# 3_STM32F103_Debugger.net
KiCad netlist of a schematic drawn in Altium Designer
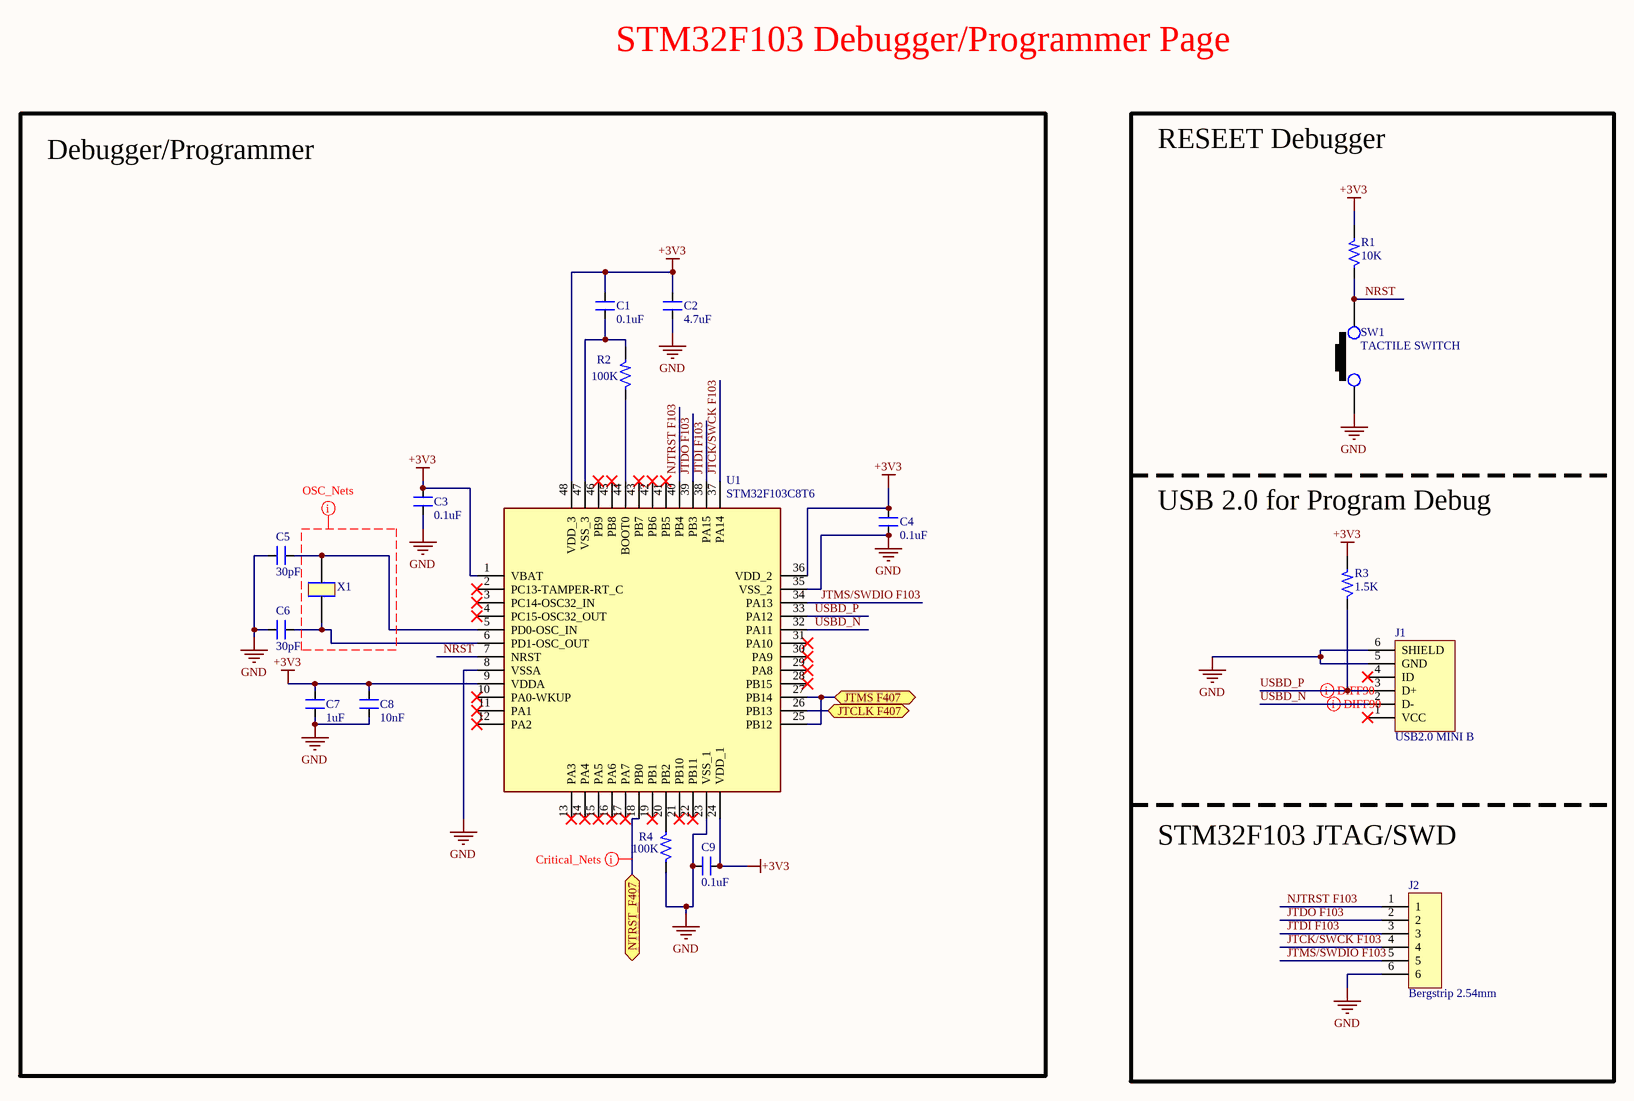
[diagram p0: [3] STM32F103 Debugger.SchDoc]

(export (version "E")
  (design (tool "Eeschema 10.0.6"))
  (components
    (comp (ref "C1")
      (value "0.1uF")
      (footprint "CAP_0805")
      (description "0.1µF ±10% 50V Ceramic Capacitor X7R 0805 (2012 Metric)")
      (fields
        (field (name "MANUFACTURER") "Samsung")
        (field (name "MANUFACTURER PART NUMBER") "CL21B104KBCNNNC")
      )
      (libsource (lib "ESTEEMPCBLIB") (part "CAP_0.1uF-50V-10%-0805"))
    )
    (comp (ref "C2")
      (value "4.7uF")
      (footprint "CAP_0805")
      (description "4.7µF ±10% 50V Ceramic Capacitor X5R 0805 (2012 Metric)")
      (fields
        (field (name "MANUFACTURER") "Yageo")
        (field (name "MANUFACTURER PART NUMBER") "GRM21BR61H475KE51L")
      )
      (libsource (lib "ESTEEMPCBLIB") (part "CAP_4.7uF-50V-10%-0805"))
    )
    (comp (ref "C3")
      (value "0.1uF")
      (footprint "CAP_0805")
      (description "0.1µF ±10% 50V Ceramic Capacitor X7R 0805 (2012 Metric)")
      (fields
        (field (name "MANUFACTURER") "Samsung")
        (field (name "MANUFACTURER PART NUMBER") "CL21B104KBCNNNC")
      )
      (libsource (lib "ESTEEMPCBLIB") (part "CAP_0.1uF-50V-10%-0805"))
    )
    (comp (ref "C4")
      (value "0.1uF")
      (footprint "CAP_0805")
      (description "0.1µF ±10% 50V Ceramic Capacitor X7R 0805 (2012 Metric)")
      (fields
        (field (name "MANUFACTURER") "Samsung")
        (field (name "MANUFACTURER PART NUMBER") "CL21B104KBCNNNC")
      )
      (libsource (lib "ESTEEMPCBLIB") (part "CAP_0.1uF-50V-10%-0805"))
    )
    (comp (ref "C5")
      (value "30pF")
      (footprint "CAP_0805")
      (description "±10% 50V Ceramic Capacitor C0G, NP0 0805 (2012 Metric)")
      (fields
        (field (name "MANUFACTURER PART NUMBER") "C0805C300K5GAC7800")
        (field (name "MANUFACTURER") "KEMET")
      )
      (libsource (lib "ESTEEMPCBLIB") (part "CAP_30pF-50V-10%-0805"))
    )
    (comp (ref "C6")
      (value "30pF")
      (footprint "CAP_0805")
      (description "±10% 50V Ceramic Capacitor C0G, NP0 0805 (2012 Metric)")
      (fields
        (field (name "MANUFACTURER PART NUMBER") "C0805C300K5GAC7800")
        (field (name "MANUFACTURER") "KEMET")
      )
      (libsource (lib "ESTEEMPCBLIB") (part "CAP_30pF-50V-10%-0805"))
    )
    (comp (ref "C7")
      (value "1uF")
      (footprint "CAP_0805")
      (description "1µF ±5% 50V Ceramic Capacitor X7R 0805 (2012 Metric)")
      (fields
        (field (name "MANUFACTURER") "Samsung")
        (field (name "MANUFACTURER PART NUMBER") "CC0805JKX7R9BB105")
      )
      (libsource (lib "ESTEEMPCBLIB") (part "CAP_1uF-50V-5%-0805"))
    )
    (comp (ref "C8")
      (value "10nF")
      (footprint "CAP_0805")
      (description "10000pF ±10% 50V Ceramic Capacitor X7R 0805 (2012 Metric)")
      (fields
        (field (name "MANUFACTURER") "Samsung")
        (field (name "MANUFACTURER PART NUMBER") "C0805C103K5RECAUTO")
      )
      (libsource (lib "ESTEEMPCBLIB") (part "CAP_10nF-50V-10%-0805"))
    )
    (comp (ref "C9")
      (value "0.1uF")
      (footprint "CAP_0805")
      (description "0.1µF ±10% 50V Ceramic Capacitor X7R 0805 (2012 Metric)")
      (fields
        (field (name "MANUFACTURER") "Samsung")
        (field (name "MANUFACTURER PART NUMBER") "CL21B104KBCNNNC")
      )
      (libsource (lib "ESTEEMPCBLIB") (part "CAP_0.1uF-50V-10%-0805"))
    )
    (comp (ref "J1")
      (value "USB2.0 MINI B")
      (footprint "CON_690-005-299-043")
      (description "USB - mini B USB 2.0 Receptacle Connector 5 Position Surface Mount, Right Angle")
      (fields
        (field (name "MANUFACTURER") "EDAC")
        (field (name "MANUFACTURER PART NUMBER") "690-005-299-043")
      )
      (libsource (lib "ESTEEMPCBLIB") (part "CON_USB2.0-MINIB-SMD"))
    )
    (comp (ref "J2")
      (value "Bergstrip 2.54mm")
      (footprint "CON6_100_59D78_TH_ST")
      (description "6 Pins, 1 Row 2.54mm Pitch, Straight bergstrip, Female")
      (fields (field (name "MANUFACTURER") "Molex") (field (name "MANUFACTURER PART NUMBER") "22-10-2061"))
      (libsource (lib "ESTEEMPCBLIB") (part "CON-BS-SKT_6X1-100-ST-TH"))
    )
    (comp (ref "R1")
      (value "10K")
      (footprint "RES_0603")
      (description "10 kOhms ±1% 0.1W, 1/10W Chip Resistor 0603 (1608 Metric) Automotive AEC-Q200 Thick Film")
      (fields (field (name "MANUFACTURER") "Walsin") (field (name "MANUFACTURER PART NUMBER") "WR06X1002FTL"))
      (libsource (lib "ESTEEMPCBLIB") (part "RES_10K-0.1W-1%-0603"))
    )
    (comp (ref "R2")
      (value "100K")
      (footprint "RES_0603")
      (description "100 kOhms ±1% 0.1W, 1/10W Chip Resistor 0603 (1608 Metric) Automotive AEC-Q200 Thick Film")
      (fields
        (field (name "MANUFACTURER") "Stackpole Electronics")
        (field (name "MANUFACTURER PART NUMBER") "RMCF0603FT100K")
      )
      (libsource (lib "ESTEEMPCBLIB") (part "RES_100K-0.1W-1%-0603"))
    )
    (comp (ref "R3")
      (value "1.5K")
      (footprint "RES_0805")
      (description "1.5 kOhms ±1% 0.125W, 1/8W Chip Resistor 0805 (2012 Metric) Thick Film")
      (fields
        (field (name "MANUFACTURER") "TE Connectivity Passive Product")
        (field (name "MANUFACTURER PART NUMBER") "CRG0805F1K5")
      )
      (libsource (lib "ESTEEMPCBLIB") (part "RES_1.5K-0.125W-1%-0805"))
    )
    (comp (ref "R4")
      (value "100K")
      (footprint "RES_0603")
      (description "100 kOhms ±1% 0.1W, 1/10W Chip Resistor 0603 (1608 Metric) Automotive AEC-Q200 Thick Film")
      (fields
        (field (name "MANUFACTURER") "Stackpole Electronics")
        (field (name "MANUFACTURER PART NUMBER") "RMCF0603FT100K")
      )
      (libsource (lib "ESTEEMPCBLIB") (part "RES_100K-0.1W-1%-0603"))
    )
    (comp (ref "SW1")
      (value "TACTILE SWITCH")
      (footprint "SW_342_SMD")
      (description "Tactile Switch SPST-NO Top Actuated Surface Mount")
      (fields
        (field (name "MANUFACTURER") "ITT C&K")
        (field (name "MANUFACTURER PART NUMBER") "RS-282G05A3-SMRT")
      )
      (libsource (lib "ESTEEMPCBLIB") (part "SW1_RS-282G05A3-SMRT-SMD"))
    )
    (comp (ref "U1")
      (value "STM32F103C8T6")
      (footprint "LQFP-48_19.6_393_58X11_SMD")
      (description "ARM® Cortex®-M3 STM32F1 Microcontroller IC 32-Bit 72MHz 64KB (64K x 8) FLASH 48-LQFP (7x7)")
      (fields (field (name "MANUFACTURER") "STMicroelectronics"))
      (libsource (lib "ESTEEMPCBLIB") (part "IC_STM32F103C8T6"))
    )
    (comp (ref "X1")
      (value "~")
      (footprint "XTAL_314_240X47_SMD")
      (description "8MHz ±30ppm Crystal 32pF 60 Ohms HC-49/US")
      (fields
        (field (name "MANUFACTURER") "Fox Electronics")
        (field (name "MANUFACTURER PART NUMBER") "ECS-80-32-5PX-TR")
      )
      (libsource (lib "ESTEEMPCBLIB") (part "XTAL_8MHZ-ECS-80-32-5PX-SMD"))
    )
  )
  (nets
    (net (code "1") (name "+3V3") (class "Default")
      (node (ref "C1") (pin "2") (pinfunction "2_2") (pintype "passive"))
      (node (ref "C2") (pin "1") (pinfunction "1_1") (pintype "passive"))
      (node (ref "C3") (pin "2") (pinfunction "2_2") (pintype "passive"))
      (node (ref "C4") (pin "2") (pinfunction "2_2") (pintype "passive"))
      (node (ref "C7") (pin "2") (pinfunction "2_2") (pintype "passive"))
      (node (ref "C8") (pin "2") (pinfunction "2_2") (pintype "passive"))
      (node (ref "C9") (pin "1") (pinfunction "1_1") (pintype "passive"))
      (node (ref "R1") (pin "2") (pinfunction "2_2") (pintype "passive"))
      (node (ref "R3") (pin "2") (pinfunction "2_2") (pintype "passive"))
      (node (ref "U1") (pin "1") (pinfunction "VBAT_1") (pintype "passive"))
      (node (ref "U1") (pin "24") (pinfunction "VDD_1_24") (pintype "passive"))
      (node (ref "U1") (pin "36") (pinfunction "VDD_2_36") (pintype "passive"))
      (node (ref "U1") (pin "48") (pinfunction "VDD_3_48") (pintype "passive"))
      (node (ref "U1") (pin "9") (pinfunction "VDDA_9") (pintype "passive"))
    )
    (net (code "2") (name "/JTCK{slash}SWCK F103") (class "Default")
      (node (ref "J2") (pin "4") (pinfunction "4_4") (pintype "passive"))
      (node (ref "U1") (pin "37") (pinfunction "PA14_37") (pintype "passive"))
    )
    (net (code "3") (name "/JTCLK F407") (class "Default")
      (node (ref "U1") (pin "26") (pinfunction "PB13_26") (pintype "passive"))
    )
    (net (code "4") (name "/JTDI F103") (class "Default")
      (node (ref "J2") (pin "3") (pinfunction "3_3") (pintype "passive"))
      (node (ref "U1") (pin "38") (pinfunction "PA15_38") (pintype "passive"))
    )
    (net (code "5") (name "/JTDO F103") (class "Default")
      (node (ref "J2") (pin "2") (pinfunction "2_2") (pintype "passive"))
      (node (ref "U1") (pin "39") (pinfunction "PB3_39") (pintype "passive"))
    )
    (net (code "6") (name "/JTMS F407") (class "Default")
      (node (ref "U1") (pin "25") (pinfunction "PB12_25") (pintype "passive"))
      (node (ref "U1") (pin "27") (pinfunction "PB14_27") (pintype "passive"))
    )
    (net (code "7") (name "/JTMS{slash}SWDIO F103") (class "Default")
      (node (ref "J2") (pin "5") (pinfunction "5_5") (pintype "passive"))
      (node (ref "U1") (pin "34") (pinfunction "PA13_34") (pintype "passive"))
    )
    (net (code "8") (name "/NJTRST F103") (class "Default")
      (node (ref "J2") (pin "1") (pinfunction "1_1") (pintype "passive"))
      (node (ref "U1") (pin "40") (pinfunction "PB4_40") (pintype "passive"))
    )
    (net (code "9") (name "/NRST") (class "Default")
      (node (ref "R1") (pin "1") (pinfunction "1_1") (pintype "passive"))
      (node (ref "SW1") (pin "2") (pinfunction "2_2") (pintype "passive"))
      (node (ref "U1") (pin "7") (pinfunction "NRST_7") (pintype "passive"))
    )
    (net (code "10") (name "/NTRST_F407") (class "Default")
      (node (ref "U1") (pin "18") (pinfunction "PB0_18") (pintype "passive"))
    )
    (net (code "11") (name "/USBD_N") (class "Default")
      (node (ref "J1") (pin "2") (pinfunction "D-_2") (pintype "passive"))
      (node (ref "U1") (pin "32") (pinfunction "PA11_32") (pintype "passive"))
    )
    (net (code "12") (name "/USBD_P") (class "Default")
      (node (ref "J1") (pin "3") (pinfunction "D+_3") (pintype "passive"))
      (node (ref "R3") (pin "1") (pinfunction "1_1") (pintype "passive"))
      (node (ref "U1") (pin "33") (pinfunction "PA12_33") (pintype "passive"))
    )
    (net (code "13") (name "GND") (class "Default")
      (node (ref "C2") (pin "2") (pinfunction "2_2") (pintype "passive"))
      (node (ref "C3") (pin "1") (pinfunction "1_1") (pintype "passive"))
      (node (ref "C4") (pin "1") (pinfunction "1_1") (pintype "passive"))
      (node (ref "C5") (pin "2") (pinfunction "2_2") (pintype "passive"))
      (node (ref "C6") (pin "2") (pinfunction "2_2") (pintype "passive"))
      (node (ref "C7") (pin "1") (pinfunction "1_1") (pintype "passive"))
      (node (ref "C8") (pin "1") (pinfunction "1_1") (pintype "passive"))
      (node (ref "C9") (pin "2") (pinfunction "2_2") (pintype "passive"))
      (node (ref "J1") (pin "5") (pinfunction "GND_5") (pintype "passive"))
      (node (ref "J1") (pin "6") (pinfunction "SHIELD_6") (pintype "passive"))
      (node (ref "J2") (pin "6") (pinfunction "6_6") (pintype "passive"))
      (node (ref "R4") (pin "1") (pinfunction "1_1") (pintype "passive"))
      (node (ref "SW1") (pin "1") (pinfunction "1_1") (pintype "passive"))
      (node (ref "U1") (pin "23") (pinfunction "VSS_1_23") (pintype "passive"))
      (node (ref "U1") (pin "35") (pinfunction "VSS_2_35") (pintype "passive"))
      (node (ref "U1") (pin "8") (pinfunction "VSSA_8") (pintype "passive"))
    )
    (net (code "14") (name "Net-(U1-BOOT0)") (class "Default")
      (node (ref "R2") (pin "1") (pinfunction "1_1") (pintype "passive"))
      (node (ref "U1") (pin "44") (pinfunction "BOOT0_44") (pintype "passive"))
    )
    (net (code "15") (name "Net-(U1-PB2)") (class "Default")
      (node (ref "R4") (pin "2") (pinfunction "2_2") (pintype "passive"))
      (node (ref "U1") (pin "20") (pinfunction "PB2_20") (pintype "passive"))
    )
    (net (code "16") (name "Net-(U1-PD0-OSC_IN)") (class "Default")
      (node (ref "C5") (pin "1") (pinfunction "1_1") (pintype "passive"))
      (node (ref "U1") (pin "5") (pinfunction "PD0-OSC_IN_5") (pintype "passive"))
      (node (ref "X1") (pin "2") (pinfunction "2_2") (pintype "passive"))
    )
    (net (code "17") (name "Net-(U1-PD1-OSC_OUT)") (class "Default")
      (node (ref "C6") (pin "1") (pinfunction "1_1") (pintype "passive"))
      (node (ref "U1") (pin "6") (pinfunction "PD1-OSC_OUT_6") (pintype "passive"))
      (node (ref "X1") (pin "1") (pinfunction "1_1") (pintype "passive"))
    )
    (net (code "18") (name "Net-(U1-VSS_3)") (class "Default")
      (node (ref "C1") (pin "1") (pinfunction "1_1") (pintype "passive"))
      (node (ref "R2") (pin "2") (pinfunction "2_2") (pintype "passive"))
      (node (ref "U1") (pin "47") (pinfunction "VSS_3_47") (pintype "passive"))
    )
    (net (code "19") (name "unconnected-(J1-ID-Pad4)") (class "Default")
      (node (ref "J1") (pin "4") (pinfunction "ID_4") (pintype "passive+no_connect"))
    )
    (net (code "20") (name "unconnected-(J1-VCC-Pad1)") (class "Default")
      (node (ref "J1") (pin "1") (pinfunction "VCC_1") (pintype "passive+no_connect"))
    )
    (net (code "21") (name "unconnected-(U1-PA0-WKUP-Pad10)") (class "Default")
      (node (ref "U1") (pin "10") (pinfunction "PA0-WKUP_10") (pintype "passive+no_connect"))
    )
    (net (code "22") (name "unconnected-(U1-PA1-Pad11)") (class "Default")
      (node (ref "U1") (pin "11") (pinfunction "PA1_11") (pintype "passive+no_connect"))
    )
    (net (code "23") (name "unconnected-(U1-PA2-Pad12)") (class "Default")
      (node (ref "U1") (pin "12") (pinfunction "PA2_12") (pintype "passive+no_connect"))
    )
    (net (code "24") (name "unconnected-(U1-PA3-Pad13)") (class "Default")
      (node (ref "U1") (pin "13") (pinfunction "PA3_13") (pintype "passive+no_connect"))
    )
    (net (code "25") (name "unconnected-(U1-PA4-Pad14)") (class "Default")
      (node (ref "U1") (pin "14") (pinfunction "PA4_14") (pintype "passive+no_connect"))
    )
    (net (code "26") (name "unconnected-(U1-PA5-Pad15)") (class "Default")
      (node (ref "U1") (pin "15") (pinfunction "PA5_15") (pintype "passive+no_connect"))
    )
    (net (code "27") (name "unconnected-(U1-PA6-Pad16)") (class "Default")
      (node (ref "U1") (pin "16") (pinfunction "PA6_16") (pintype "passive+no_connect"))
    )
    (net (code "28") (name "unconnected-(U1-PA7-Pad17)") (class "Default")
      (node (ref "U1") (pin "17") (pinfunction "PA7_17") (pintype "passive+no_connect"))
    )
    (net (code "29") (name "unconnected-(U1-PA8-Pad29)") (class "Default")
      (node (ref "U1") (pin "29") (pinfunction "PA8_29") (pintype "passive+no_connect"))
    )
    (net (code "30") (name "unconnected-(U1-PA9-Pad30)") (class "Default")
      (node (ref "U1") (pin "30") (pinfunction "PA9_30") (pintype "passive+no_connect"))
    )
    (net (code "31") (name "unconnected-(U1-PA10-Pad31)") (class "Default")
      (node (ref "U1") (pin "31") (pinfunction "PA10_31") (pintype "passive+no_connect"))
    )
    (net (code "32") (name "unconnected-(U1-PB1-Pad19)") (class "Default")
      (node (ref "U1") (pin "19") (pinfunction "PB1_19") (pintype "passive+no_connect"))
    )
    (net (code "33") (name "unconnected-(U1-PB5-Pad41)") (class "Default")
      (node (ref "U1") (pin "41") (pinfunction "PB5_41") (pintype "passive+no_connect"))
    )
    (net (code "34") (name "unconnected-(U1-PB6-Pad42)") (class "Default")
      (node (ref "U1") (pin "42") (pinfunction "PB6_42") (pintype "passive+no_connect"))
    )
    (net (code "35") (name "unconnected-(U1-PB7-Pad43)") (class "Default")
      (node (ref "U1") (pin "43") (pinfunction "PB7_43") (pintype "passive+no_connect"))
    )
    (net (code "36") (name "unconnected-(U1-PB8-Pad45)") (class "Default")
      (node (ref "U1") (pin "45") (pinfunction "PB8_45") (pintype "passive+no_connect"))
    )
    (net (code "37") (name "unconnected-(U1-PB9-Pad46)") (class "Default")
      (node (ref "U1") (pin "46") (pinfunction "PB9_46") (pintype "passive+no_connect"))
    )
    (net (code "38") (name "unconnected-(U1-PB10-Pad21)") (class "Default")
      (node (ref "U1") (pin "21") (pinfunction "PB10_21") (pintype "passive+no_connect"))
    )
    (net (code "39") (name "unconnected-(U1-PB11-Pad22)") (class "Default")
      (node (ref "U1") (pin "22") (pinfunction "PB11_22") (pintype "passive+no_connect"))
    )
    (net (code "40") (name "unconnected-(U1-PB15-Pad28)") (class "Default")
      (node (ref "U1") (pin "28") (pinfunction "PB15_28") (pintype "passive+no_connect"))
    )
    (net (code "41") (name "unconnected-(U1-PC13-TAMPER-RT_C-Pad2)") (class "Default")
      (node (ref "U1") (pin "2") (pinfunction "PC13-TAMPER-RT_C_2") (pintype "passive+no_connect"))
    )
    (net (code "42") (name "unconnected-(U1-PC14-OSC32_IN-Pad3)") (class "Default")
      (node (ref "U1") (pin "3") (pinfunction "PC14-OSC32_IN_3") (pintype "passive+no_connect"))
    )
    (net (code "43") (name "unconnected-(U1-PC15-OSC32_OUT-Pad4)") (class "Default")
      (node (ref "U1") (pin "4") (pinfunction "PC15-OSC32_OUT_4") (pintype "passive+no_connect"))
    )
  )
)
